# 6_LIN.net
KiCad netlist of a schematic drawn in EAGLE
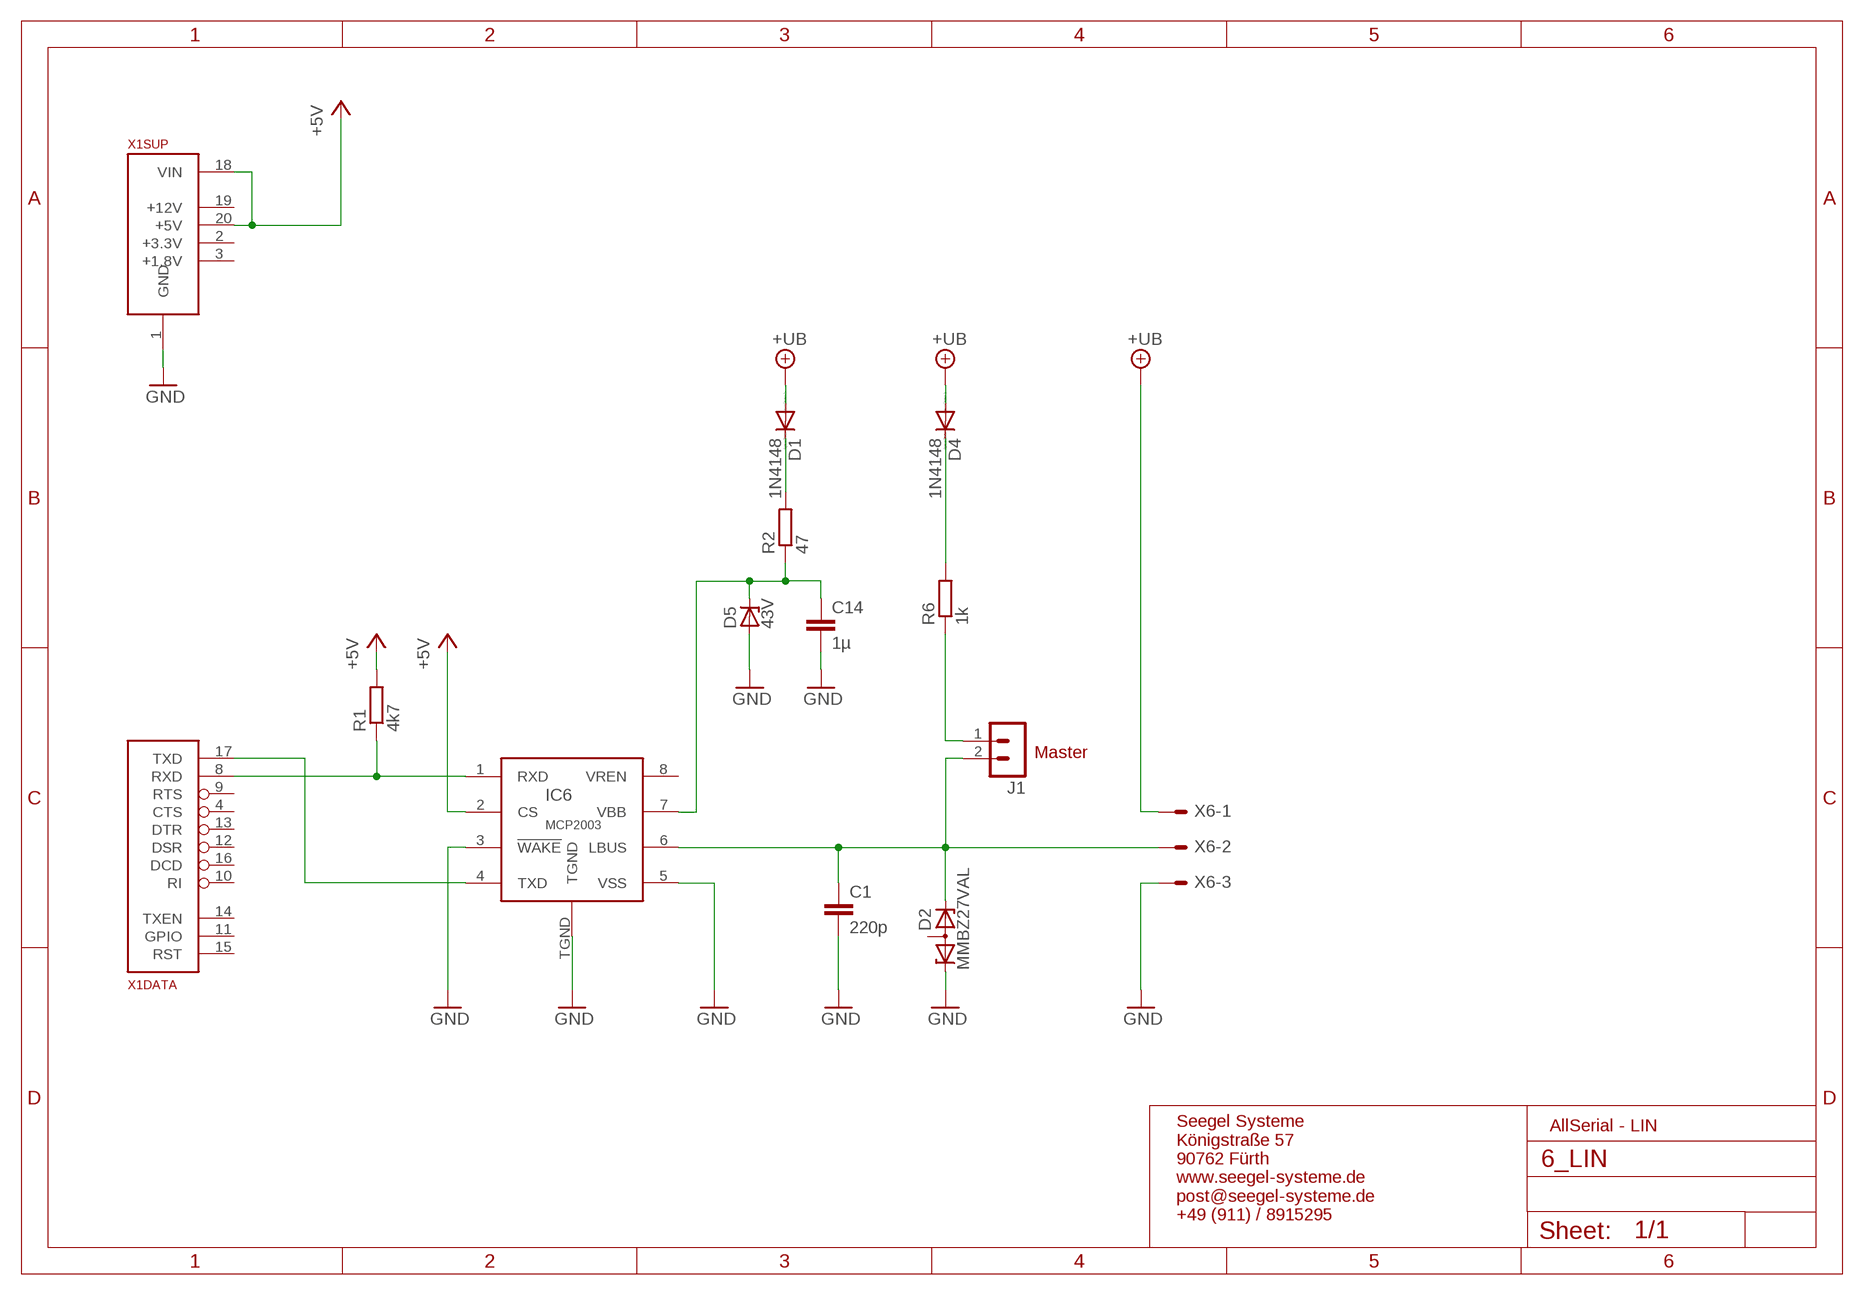
[diagram p0: schematic, sheet 1]

(export (version "E")
  (design (tool "Eeschema 10.0.6"))
  (components
    (comp (ref "C1")
      (value "220p")
      (footprint "eagle-import:C0805")
      (libsource (lib "eagle-import") (part "C-EUC0805"))
    )
    (comp (ref "C14")
      (value "1µ")
      (footprint "eagle-import:C0805")
      (libsource (lib "eagle-import") (part "C-EUC0805"))
    )
    (comp (ref "D1")
      (value "1N4148")
      (footprint "eagle-import:MINIMELF")
      (libsource (lib "eagle-import") (part "DIODE-MINIMELF"))
    )
    (comp (ref "D2")
      (value "MMBZ27VAL")
      (footprint "eagle-import:SOT23")
      (libsource (lib "eagle-import") (part "MMBZAL27V"))
    )
    (comp (ref "D4")
      (value "1N4148")
      (footprint "eagle-import:MINIMELF")
      (libsource (lib "eagle-import") (part "DIODE-MINIMELF"))
    )
    (comp (ref "D5")
      (value "43V")
      (footprint "eagle-import:SOD80C")
      (libsource (lib "eagle-import") (part "ZENER-DIODESOD80C"))
    )
    (comp (ref "IC6")
      (value "MCP2003")
      (footprint "eagle-import:SOIC8T")
      (libsource (lib "eagle-import") (part "MCP2003"))
    )
    (comp (ref "J1")
      (value "MA02-1W")
      (footprint "eagle-import:MA02-W")
      (libsource (lib "eagle-import") (part "MA02-1W"))
    )
    (comp (ref "R1")
      (value "4k7")
      (footprint "eagle-import:R0805")
      (libsource (lib "eagle-import") (part "R-EU_R0805"))
    )
    (comp (ref "R2")
      (value "47")
      (footprint "eagle-import:R0805")
      (libsource (lib "eagle-import") (part "R-EU_R0805"))
    )
    (comp (ref "R6")
      (value "1k")
      (footprint "eagle-import:R0805")
      (libsource (lib "eagle-import") (part "R-EU_R0805"))
    )
    (comp (ref "X1")
      (value "ALLSERIALSLAVE")
      (footprint "eagle-import:DAUGHTER-THT")
      (libsource (lib "eagle-import") (part "ALLSERIALSLAVE"))
    )
    (comp (ref "X6")
      (value "AKL18X-03W")
      (footprint "eagle-import:AKL182-03")
      (libsource (lib "eagle-import") (part "AKL18X-03W"))
    )
  )
  (nets
    (net (code "1") (name "+5V") (class "Default")
      (node (ref "IC6") (pin "2") (pinfunction "CS_2") (pintype "input"))
      (node (ref "R1") (pin "2") (pinfunction "2_2") (pintype "passive"))
      (node (ref "X1") (pin "18") (pinfunction "VIN_18") (pintype "bidirectional"))
      (node (ref "X1") (pin "20") (pinfunction "+5V_20") (pintype "bidirectional"))
    )
    (net (code "2") (name "+UB") (class "Default")
      (node (ref "D1") (pin "A") (pinfunction "A_A") (pintype "passive"))
      (node (ref "D4") (pin "A") (pinfunction "A_A") (pintype "passive"))
      (node (ref "X6") (pin "P$1") (pinfunction "S_P$1") (pintype "passive"))
    )
    (net (code "3") (name "GND") (class "Default")
      (node (ref "C1") (pin "2") (pinfunction "2_2") (pintype "passive"))
      (node (ref "C14") (pin "2") (pinfunction "2_2") (pintype "passive"))
      (node (ref "D2") (pin "1") (pinfunction "K1_1") (pintype "passive"))
      (node (ref "D5") (pin "A") (pinfunction "A_A") (pintype "passive"))
      (node (ref "IC6") (pin "3") (pinfunction "~{WAKE}_3") (pintype "input"))
      (node (ref "IC6") (pin "5") (pinfunction "VSS_5") (pintype "power_in"))
      (node (ref "IC6") (pin "TGND") (pinfunction "TGND_TGND") (pintype "power_in"))
      (node (ref "X1") (pin "1") (pinfunction "GND_1") (pintype "bidirectional"))
      (node (ref "X6") (pin "P$3") (pinfunction "S_P$3") (pintype "passive"))
    )
    (net (code "4") (name "Net-(D1-PadC)") (class "Default")
      (node (ref "D1") (pin "C") (pinfunction "C_C") (pintype "passive"))
      (node (ref "R2") (pin "2") (pinfunction "2_2") (pintype "passive"))
    )
    (net (code "5") (name "Net-(D2-K2)") (class "Default")
      (node (ref "C1") (pin "1") (pinfunction "1_1") (pintype "passive"))
      (node (ref "D2") (pin "2") (pinfunction "K2_2") (pintype "passive"))
      (node (ref "IC6") (pin "6") (pinfunction "LBUS_6") (pintype "bidirectional"))
      (node (ref "J1") (pin "2") (pinfunction "2_2") (pintype "passive"))
      (node (ref "X6") (pin "P$2") (pinfunction "S_P$2") (pintype "passive"))
    )
    (net (code "6") (name "Net-(D4-PadC)") (class "Default")
      (node (ref "D4") (pin "C") (pinfunction "C_C") (pintype "passive"))
      (node (ref "R6") (pin "2") (pinfunction "2_2") (pintype "passive"))
    )
    (net (code "7") (name "Net-(IC6-RXD)") (class "Default")
      (node (ref "IC6") (pin "1") (pinfunction "RXD_1") (pintype "input"))
      (node (ref "R1") (pin "1") (pinfunction "1_1") (pintype "passive"))
      (node (ref "X1") (pin "8") (pinfunction "RXD_8") (pintype "input"))
    )
    (net (code "8") (name "Net-(IC6-TXD)") (class "Default")
      (node (ref "IC6") (pin "4") (pinfunction "TXD_4") (pintype "output"))
      (node (ref "X1") (pin "17") (pinfunction "TXD_17") (pintype "output"))
    )
    (net (code "9") (name "Net-(IC6-VBB)") (class "Default")
      (node (ref "C14") (pin "1") (pinfunction "1_1") (pintype "passive"))
      (node (ref "D5") (pin "C") (pinfunction "C_C") (pintype "passive"))
      (node (ref "IC6") (pin "7") (pinfunction "VBB_7") (pintype "power_in"))
      (node (ref "R2") (pin "1") (pinfunction "1_1") (pintype "passive"))
    )
    (net (code "10") (name "Net-(J1-Pad1)") (class "Default")
      (node (ref "J1") (pin "1") (pinfunction "1_1") (pintype "passive"))
      (node (ref "R6") (pin "1") (pinfunction "1_1") (pintype "passive"))
    )
    (net (code "11") (name "unconnected-(D2-A-Pad3)") (class "Default")
      (node (ref "D2") (pin "3") (pinfunction "A_3") (pintype "passive"))
    )
    (net (code "12") (name "unconnected-(IC6-VREN-Pad8)") (class "Default")
      (node (ref "IC6") (pin "8") (pinfunction "VREN_8") (pintype "output"))
    )
    (net (code "13") (name "unconnected-(X1A-CTS-Pad4)") (class "Default")
      (node (ref "X1") (pin "4") (pinfunction "CTS_4") (pintype "input"))
    )
    (net (code "14") (name "unconnected-(X1A-DCD-Pad16)") (class "Default")
      (node (ref "X1") (pin "16") (pinfunction "DCD_16") (pintype "input"))
    )
    (net (code "15") (name "unconnected-(X1A-DSR-Pad12)") (class "Default")
      (node (ref "X1") (pin "12") (pinfunction "DSR_12") (pintype "input"))
    )
    (net (code "16") (name "unconnected-(X1A-DTR-Pad13)") (class "Default")
      (node (ref "X1") (pin "13") (pinfunction "DTR_13") (pintype "output"))
    )
    (net (code "17") (name "unconnected-(X1A-GPIO-Pad11)") (class "Default")
      (node (ref "X1") (pin "11") (pinfunction "GPIO_11") (pintype "bidirectional"))
    )
    (net (code "18") (name "unconnected-(X1A-RI-Pad10)") (class "Default")
      (node (ref "X1") (pin "10") (pinfunction "RI_10") (pintype "input"))
    )
    (net (code "19") (name "unconnected-(X1A-RST-Pad15)") (class "Default")
      (node (ref "X1") (pin "15") (pinfunction "RST_15") (pintype "bidirectional"))
    )
    (net (code "20") (name "unconnected-(X1A-RTS-Pad9)") (class "Default")
      (node (ref "X1") (pin "9") (pinfunction "RTS_9") (pintype "output"))
    )
    (net (code "21") (name "unconnected-(X1A-TXEN-Pad14)") (class "Default")
      (node (ref "X1") (pin "14") (pinfunction "TXEN_14") (pintype "output"))
    )
    (net (code "22") (name "unconnected-(X1B-+1.8V-Pad3)") (class "Default")
      (node (ref "X1") (pin "3") (pinfunction "+1.8V_3") (pintype "bidirectional"))
    )
    (net (code "23") (name "unconnected-(X1B-+3.3V-Pad2)") (class "Default")
      (node (ref "X1") (pin "2") (pinfunction "+3.3V_2") (pintype "bidirectional"))
    )
    (net (code "24") (name "unconnected-(X1B-+12V-Pad19)") (class "Default")
      (node (ref "X1") (pin "19") (pinfunction "+12V_19") (pintype "bidirectional"))
    )
  )
)
